# SCH_test_TGT_2024-01-07.net
KiCad netlist of a schematic drawn in EasyEDA
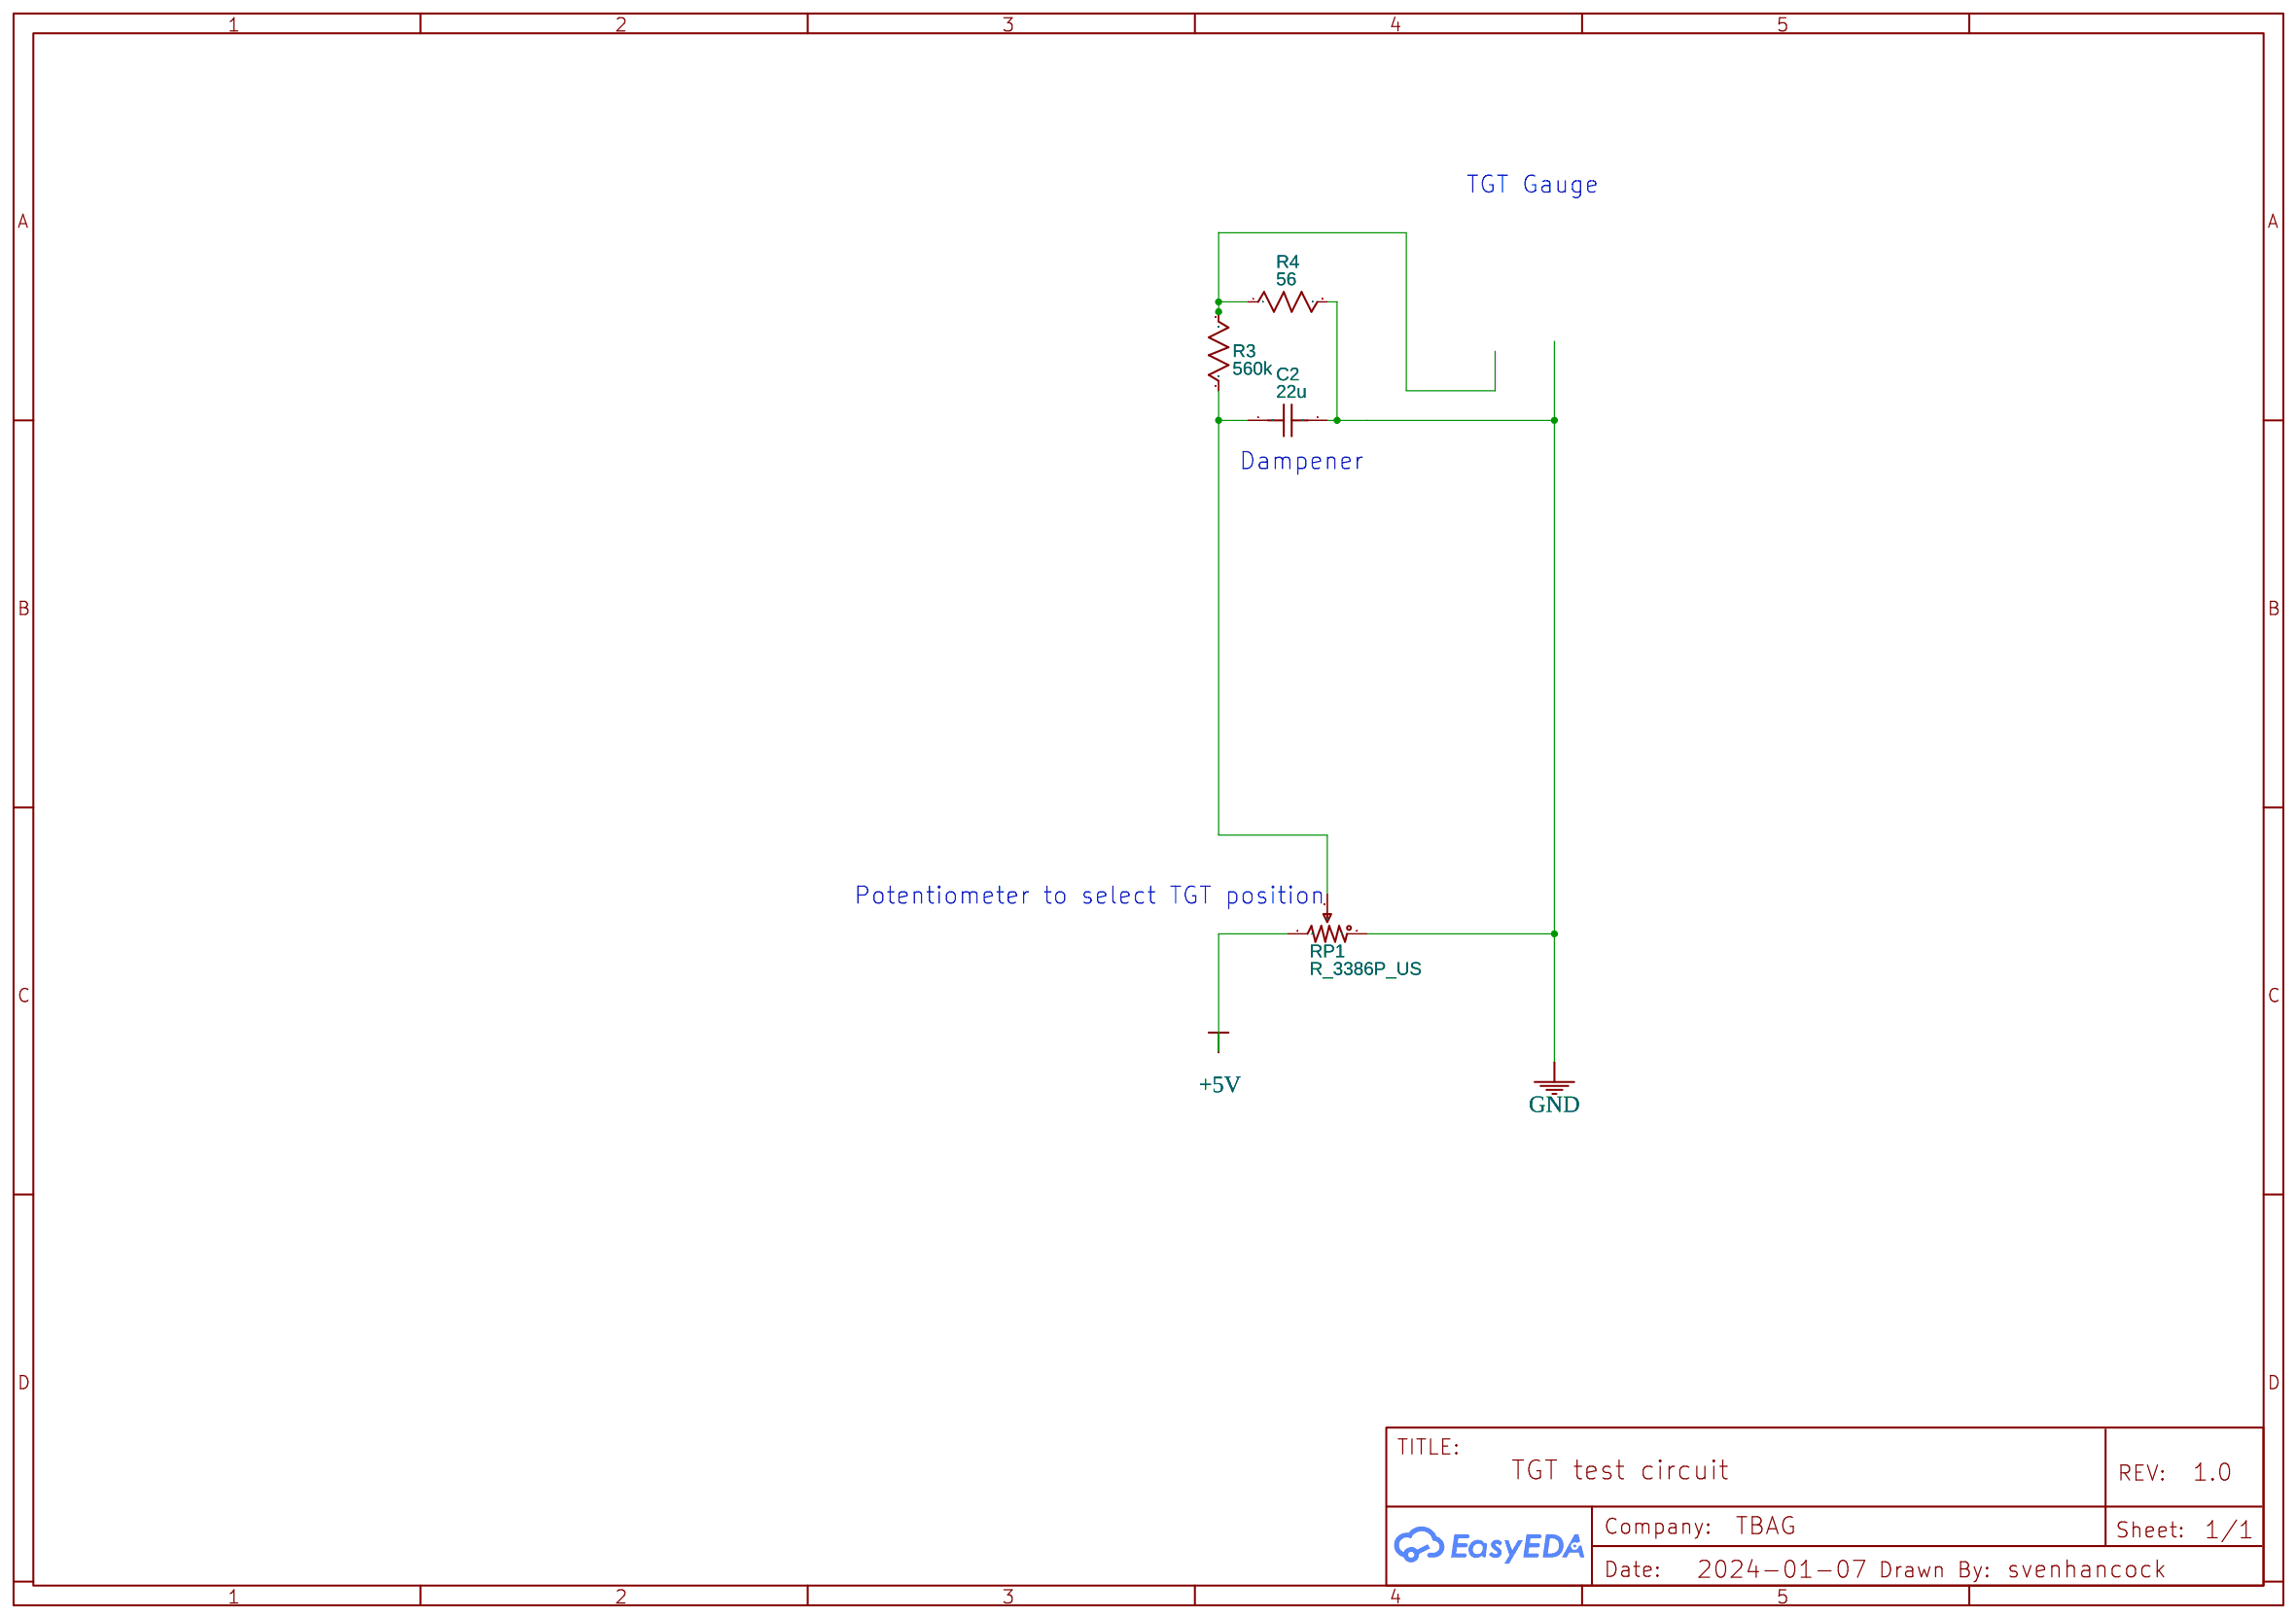
[diagram p0: schematic sheet]

(export (version "E")
  (design (tool "Eeschema 10.0.6"))
  (components
    (comp (ref "C2") (value "22u") (libsource (lib "") (part "C_0603_US")))
    (comp (ref "R3") (value "560k") (libsource (lib "") (part "R_0603_US")))
    (comp (ref "R4") (value "56") (libsource (lib "") (part "R_0603_US_1")))
    (comp (ref "RP1") (value "R_3386P_US") (libsource (lib "") (part "R_3386P_US")))
  )
  (nets
    (net (code "1") (name "+5V") (class "Default")
      (node (ref "RP1") (pin "3") (pinfunction "3_3") (pintype "unspecified"))
    )
    (net (code "2") (name "GND") (class "Default")
      (node (ref "C2") (pin "2") (pinfunction "2_2") (pintype "unspecified"))
      (node (ref "R4") (pin "2") (pinfunction "2_2") (pintype "unspecified"))
      (node (ref "RP1") (pin "1") (pinfunction "1_1") (pintype "unspecified"))
    )
    (net (code "3") (name "Net-(C2-Pad1)") (class "Default")
      (node (ref "C2") (pin "1") (pinfunction "1_1") (pintype "unspecified"))
      (node (ref "R3") (pin "1") (pinfunction "1_1") (pintype "unspecified"))
      (node (ref "RP1") (pin "2") (pinfunction "2_2") (pintype "unspecified"))
    )
    (net (code "4") (name "Net-(R3-Pad2)") (class "Default")
      (node (ref "R3") (pin "2") (pinfunction "2_2") (pintype "unspecified"))
      (node (ref "R4") (pin "1") (pinfunction "1_1") (pintype "unspecified"))
    )
  )
)
